# iterasi1.net
KiCad netlist of a schematic drawn in EAGLE
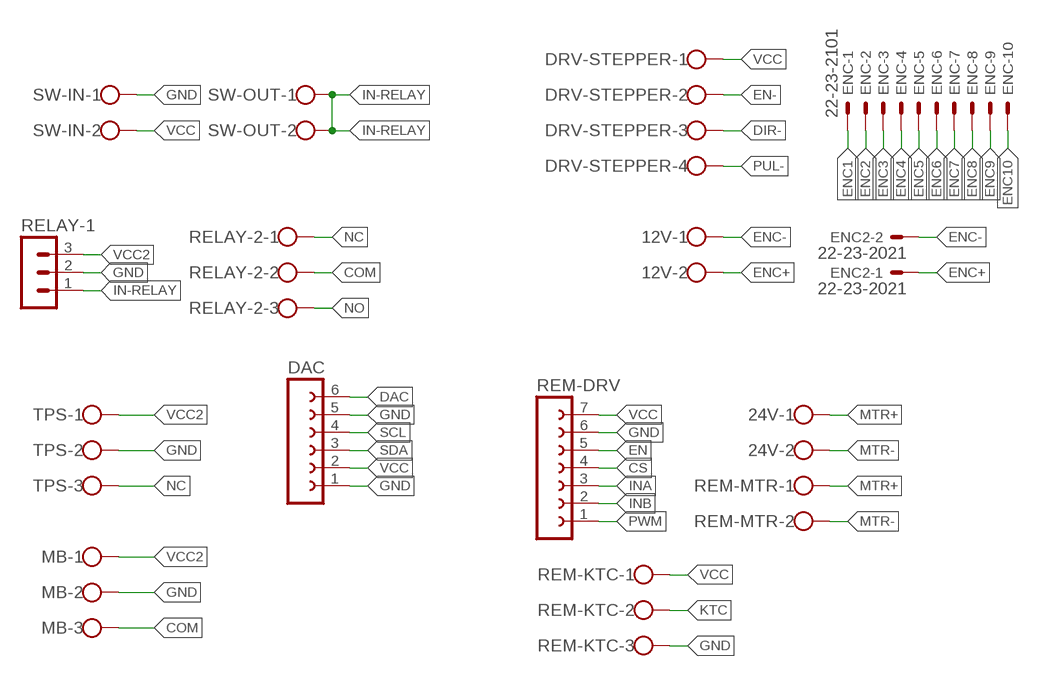
[diagram p0: schematic, sheet 1]

(export (version "E")
  (design (tool "Eeschema 10.0.6"))
  (components
    (comp (ref "12V")
      (value "W237-102")
      (footprint "eagle-import:W237-102")
      (fields (field (name "MPN") "237-102"))
      (libsource (lib "eagle-import") (part "W237-102"))
    )
    (comp (ref "24V")
      (value "W237-102")
      (footprint "eagle-import:W237-102")
      (fields (field (name "MPN") "237-102"))
      (libsource (lib "eagle-import") (part "W237-102"))
    )
    (comp (ref "DAC")
      (value "FE06-1")
      (footprint "eagle-import:FE06")
      (libsource (lib "eagle-import") (part "FE06-1"))
    )
    (comp (ref "DRV-STEPPER")
      (value "W237-4")
      (footprint "eagle-import:W237-4")
      (libsource (lib "eagle-import") (part "W237-4"))
    )
    (comp (ref "ENC")
      (value "22-23-2101")
      (footprint "eagle-import:22-23-2101")
      (fields (field (name "MF") "MOLEX"))
      (libsource (lib "eagle-import") (part "22-23-2101"))
    )
    (comp (ref "ENC2")
      (value "22-23-2021")
      (footprint "eagle-import:22-23-2021")
      (fields (field (name "MF") "MOLEX"))
      (libsource (lib "eagle-import") (part "22-23-2021"))
    )
    (comp (ref "MB")
      (value "W237-103")
      (footprint "eagle-import:W237-103")
      (fields (field (name "MPN") "237-103"))
      (libsource (lib "eagle-import") (part "W237-103"))
    )
    (comp (ref "RELAY-1")
      (value "MA03-1")
      (footprint "eagle-import:MA03-1")
      (libsource (lib "eagle-import") (part "MA03-1"))
    )
    (comp (ref "RELAY-2")
      (value "W237-103")
      (footprint "eagle-import:W237-103")
      (fields (field (name "MPN") "237-103"))
      (libsource (lib "eagle-import") (part "W237-103"))
    )
    (comp (ref "REM-DRV")
      (value "FE07-1")
      (footprint "eagle-import:FE07")
      (libsource (lib "eagle-import") (part "FE07-1"))
    )
    (comp (ref "REM-KTC")
      (value "W237-103")
      (footprint "eagle-import:W237-103")
      (fields (field (name "MPN") "237-103"))
      (libsource (lib "eagle-import") (part "W237-103"))
    )
    (comp (ref "REM-MTR")
      (value "W237-102")
      (footprint "eagle-import:W237-102")
      (fields (field (name "MPN") "237-102"))
      (libsource (lib "eagle-import") (part "W237-102"))
    )
    (comp (ref "SW-IN")
      (value "W237-102")
      (footprint "eagle-import:W237-102")
      (fields (field (name "MPN") "237-102"))
      (libsource (lib "eagle-import") (part "W237-102"))
    )
    (comp (ref "SW-OUT")
      (value "W237-102")
      (footprint "eagle-import:W237-102")
      (fields (field (name "MPN") "237-102"))
      (libsource (lib "eagle-import") (part "W237-102"))
    )
    (comp (ref "TPS")
      (value "W237-103")
      (footprint "eagle-import:W237-103")
      (fields (field (name "MPN") "237-103"))
      (libsource (lib "eagle-import") (part "W237-103"))
    )
  )
  (nets
    (net (code "1") (name "COM") (class "Default")
      (node (ref "MB") (pin "3") (pinfunction "KL_3") (pintype "passive"))
      (node (ref "RELAY-2") (pin "2") (pinfunction "KL_2") (pintype "passive"))
    )
    (net (code "2") (name "CS") (class "Default")
      (node (ref "REM-DRV") (pin "4") (pinfunction "4_4") (pintype "passive"))
    )
    (net (code "3") (name "DAC") (class "Default")
      (node (ref "DAC") (pin "6") (pinfunction "6_6") (pintype "passive"))
    )
    (net (code "4") (name "DIR-") (class "Default")
      (node (ref "DRV-STEPPER") (pin "3") (pinfunction "KL_3") (pintype "passive"))
    )
    (net (code "5") (name "EN") (class "Default")
      (node (ref "REM-DRV") (pin "5") (pinfunction "5_5") (pintype "passive"))
    )
    (net (code "6") (name "EN-") (class "Default")
      (node (ref "DRV-STEPPER") (pin "2") (pinfunction "KL_2") (pintype "passive"))
    )
    (net (code "7") (name "ENC+") (class "Default")
      (node (ref "12V") (pin "2") (pinfunction "KL_2") (pintype "passive"))
      (node (ref "ENC2") (pin "1") (pinfunction "S_1") (pintype "passive"))
    )
    (net (code "8") (name "ENC-") (class "Default")
      (node (ref "12V") (pin "1") (pinfunction "KL_1") (pintype "passive"))
      (node (ref "ENC2") (pin "2") (pinfunction "S_2") (pintype "passive"))
    )
    (net (code "9") (name "ENC1") (class "Default")
      (node (ref "ENC") (pin "1") (pinfunction "S_1") (pintype "passive"))
    )
    (net (code "10") (name "ENC2") (class "Default")
      (node (ref "ENC") (pin "2") (pinfunction "S_2") (pintype "passive"))
    )
    (net (code "11") (name "ENC3") (class "Default")
      (node (ref "ENC") (pin "3") (pinfunction "S_3") (pintype "passive"))
    )
    (net (code "12") (name "ENC4") (class "Default")
      (node (ref "ENC") (pin "4") (pinfunction "S_4") (pintype "passive"))
    )
    (net (code "13") (name "ENC5") (class "Default")
      (node (ref "ENC") (pin "5") (pinfunction "S_5") (pintype "passive"))
    )
    (net (code "14") (name "ENC6") (class "Default")
      (node (ref "ENC") (pin "6") (pinfunction "S_6") (pintype "passive"))
    )
    (net (code "15") (name "ENC7") (class "Default")
      (node (ref "ENC") (pin "7") (pinfunction "S_7") (pintype "passive"))
    )
    (net (code "16") (name "ENC8") (class "Default")
      (node (ref "ENC") (pin "8") (pinfunction "S_8") (pintype "passive"))
    )
    (net (code "17") (name "ENC9") (class "Default")
      (node (ref "ENC") (pin "9") (pinfunction "S_9") (pintype "passive"))
    )
    (net (code "18") (name "ENC10") (class "Default")
      (node (ref "ENC") (pin "10") (pinfunction "S_10") (pintype "passive"))
    )
    (net (code "19") (name "GND") (class "Default")
      (node (ref "DAC") (pin "1") (pinfunction "1_1") (pintype "passive"))
      (node (ref "DAC") (pin "5") (pinfunction "5_5") (pintype "passive"))
      (node (ref "MB") (pin "2") (pinfunction "KL_2") (pintype "passive"))
      (node (ref "RELAY-1") (pin "2") (pinfunction "2_2") (pintype "passive"))
      (node (ref "REM-DRV") (pin "6") (pinfunction "6_6") (pintype "passive"))
      (node (ref "REM-KTC") (pin "3") (pinfunction "KL_3") (pintype "passive"))
      (node (ref "SW-IN") (pin "1") (pinfunction "KL_1") (pintype "passive"))
      (node (ref "TPS") (pin "2") (pinfunction "KL_2") (pintype "passive"))
    )
    (net (code "20") (name "IN-RELAY") (class "Default")
      (node (ref "RELAY-1") (pin "1") (pinfunction "1_1") (pintype "passive"))
      (node (ref "SW-OUT") (pin "1") (pinfunction "KL_1") (pintype "passive"))
      (node (ref "SW-OUT") (pin "2") (pinfunction "KL_2") (pintype "passive"))
    )
    (net (code "21") (name "INA") (class "Default")
      (node (ref "REM-DRV") (pin "3") (pinfunction "3_3") (pintype "passive"))
    )
    (net (code "22") (name "INB") (class "Default")
      (node (ref "REM-DRV") (pin "2") (pinfunction "2_2") (pintype "passive"))
    )
    (net (code "23") (name "KTC") (class "Default")
      (node (ref "REM-KTC") (pin "2") (pinfunction "KL_2") (pintype "passive"))
    )
    (net (code "24") (name "MTR+") (class "Default")
      (node (ref "24V") (pin "1") (pinfunction "KL_1") (pintype "passive"))
      (node (ref "REM-MTR") (pin "1") (pinfunction "KL_1") (pintype "passive"))
    )
    (net (code "25") (name "MTR-") (class "Default")
      (node (ref "24V") (pin "2") (pinfunction "KL_2") (pintype "passive"))
      (node (ref "REM-MTR") (pin "2") (pinfunction "KL_2") (pintype "passive"))
    )
    (net (code "26") (name "NC") (class "Default")
      (node (ref "RELAY-2") (pin "1") (pinfunction "KL_1") (pintype "passive"))
      (node (ref "TPS") (pin "3") (pinfunction "KL_3") (pintype "passive"))
    )
    (net (code "27") (name "NO") (class "Default")
      (node (ref "RELAY-2") (pin "3") (pinfunction "KL_3") (pintype "passive"))
    )
    (net (code "28") (name "PUL-") (class "Default")
      (node (ref "DRV-STEPPER") (pin "4") (pinfunction "KL_4") (pintype "passive"))
    )
    (net (code "29") (name "PWM") (class "Default")
      (node (ref "REM-DRV") (pin "1") (pinfunction "1_1") (pintype "passive"))
    )
    (net (code "30") (name "SCL") (class "Default")
      (node (ref "DAC") (pin "4") (pinfunction "4_4") (pintype "passive"))
    )
    (net (code "31") (name "SDA") (class "Default")
      (node (ref "DAC") (pin "3") (pinfunction "3_3") (pintype "passive"))
    )
    (net (code "32") (name "VCC") (class "Default")
      (node (ref "DAC") (pin "2") (pinfunction "2_2") (pintype "passive"))
      (node (ref "DRV-STEPPER") (pin "1") (pinfunction "KL_1") (pintype "passive"))
      (node (ref "REM-DRV") (pin "7") (pinfunction "7_7") (pintype "passive"))
      (node (ref "REM-KTC") (pin "1") (pinfunction "KL_1") (pintype "passive"))
      (node (ref "SW-IN") (pin "2") (pinfunction "KL_2") (pintype "passive"))
    )
    (net (code "33") (name "VCC2") (class "Default")
      (node (ref "MB") (pin "1") (pinfunction "KL_1") (pintype "passive"))
      (node (ref "RELAY-1") (pin "3") (pinfunction "3_3") (pintype "passive"))
      (node (ref "TPS") (pin "1") (pinfunction "KL_1") (pintype "passive"))
    )
  )
)
